# DC-DC_Converter_Module_V1.net
KiCad netlist of a schematic drawn in EAGLE
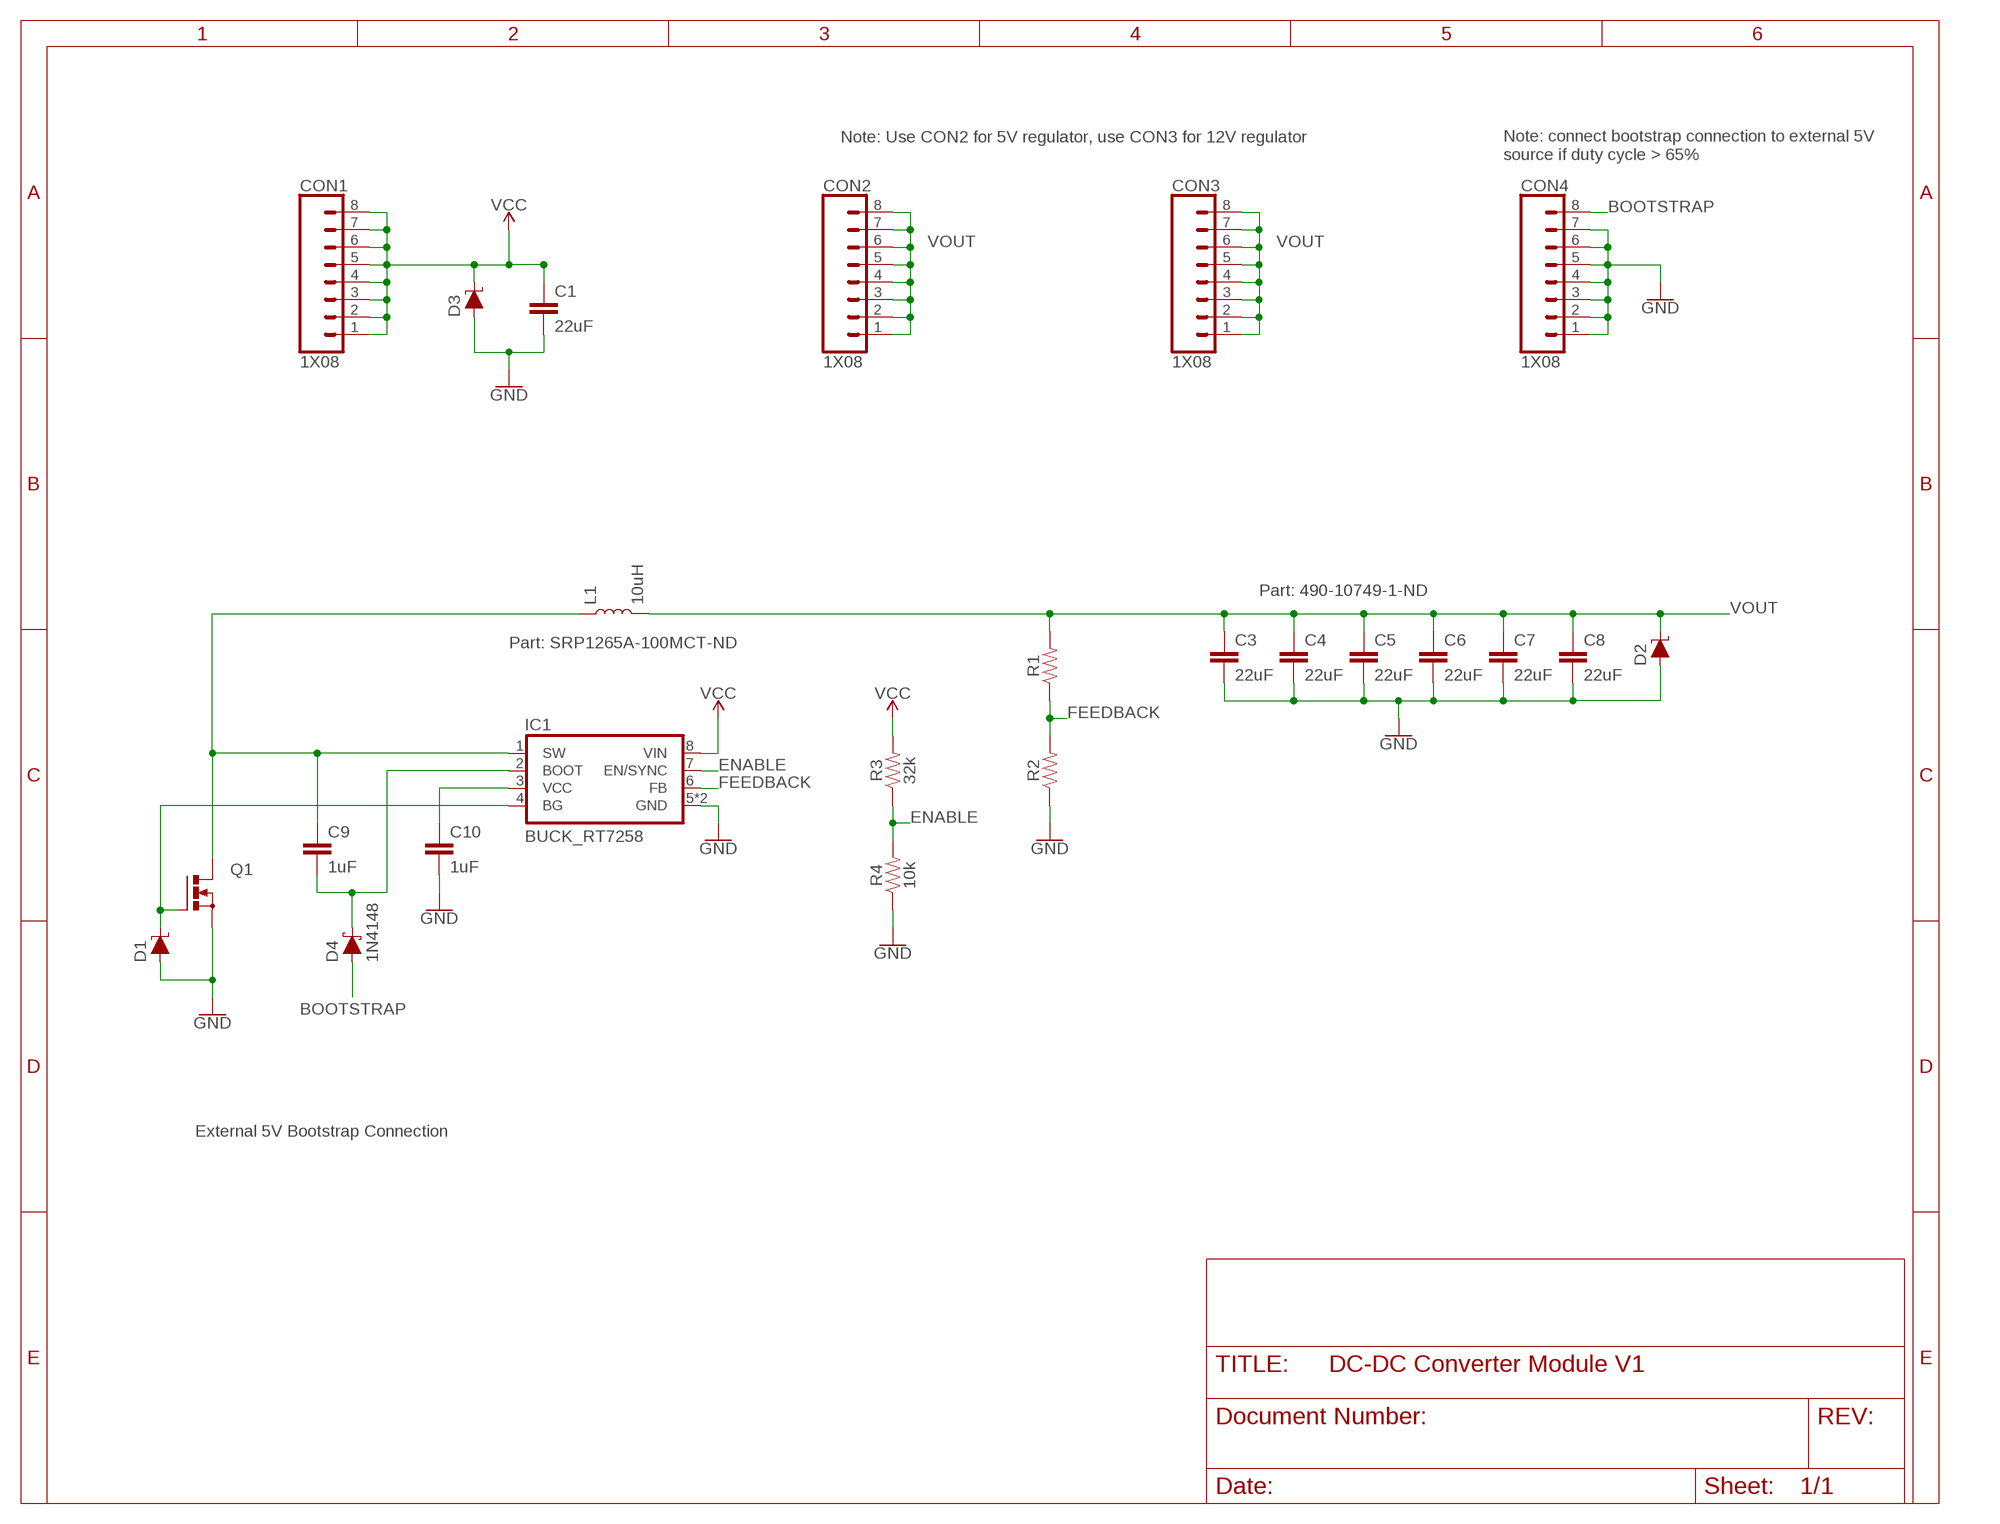
[diagram p0: schematic, sheet 1]

(export (version "E")
  (design (tool "Eeschema 10.0.6"))
  (components
    (comp (ref "C1")
      (value "22uF")
      (footprint "eagle-import:1210")
      (libsource (lib "eagle-import") (part "CAPACITOR_1210"))
    )
    (comp (ref "C3")
      (value "22uF")
      (footprint "eagle-import:0805")
      (libsource (lib "eagle-import") (part "CAPACITOR_0805"))
    )
    (comp (ref "C4")
      (value "22uF")
      (footprint "eagle-import:0805")
      (libsource (lib "eagle-import") (part "CAPACITOR_0805"))
    )
    (comp (ref "C5")
      (value "22uF")
      (footprint "eagle-import:0805")
      (libsource (lib "eagle-import") (part "CAPACITOR_0805"))
    )
    (comp (ref "C6")
      (value "22uF")
      (footprint "eagle-import:0805")
      (libsource (lib "eagle-import") (part "CAPACITOR_0805"))
    )
    (comp (ref "C7")
      (value "22uF")
      (footprint "eagle-import:0805")
      (libsource (lib "eagle-import") (part "CAPACITOR_0805"))
    )
    (comp (ref "C8")
      (value "22uF")
      (footprint "eagle-import:0805")
      (libsource (lib "eagle-import") (part "CAPACITOR_0805"))
    )
    (comp (ref "C9")
      (value "1uF")
      (footprint "eagle-import:0805")
      (libsource (lib "eagle-import") (part "CAPACITOR_0805"))
    )
    (comp (ref "C10")
      (value "1uF")
      (footprint "eagle-import:0805")
      (libsource (lib "eagle-import") (part "CAPACITOR_0805"))
    )
    (comp (ref "CON1")
      (value "1X08")
      (footprint "eagle-import:1X08")
      (libsource (lib "eagle-import") (part "1X08"))
    )
    (comp (ref "CON2")
      (value "1X08")
      (footprint "eagle-import:1X08")
      (libsource (lib "eagle-import") (part "1X08"))
    )
    (comp (ref "CON3")
      (value "1X08")
      (footprint "eagle-import:1X08")
      (libsource (lib "eagle-import") (part "1X08"))
    )
    (comp (ref "CON4")
      (value "1X08")
      (footprint "eagle-import:1X08")
      (libsource (lib "eagle-import") (part "1X08"))
    )
    (comp (ref "D1")
      (value "DIODE_TVS_DO-214AA")
      (footprint "eagle-import:DO214AA")
      (libsource (lib "eagle-import") (part "DIODE_TVS_DO-214AA"))
    )
    (comp (ref "D2")
      (value "DIODE_TVS_DO-214AA")
      (footprint "eagle-import:DO214AA")
      (libsource (lib "eagle-import") (part "DIODE_TVS_DO-214AA"))
    )
    (comp (ref "D3")
      (value "DIODE_TVS_DO-214AA")
      (footprint "eagle-import:DO214AA")
      (libsource (lib "eagle-import") (part "DIODE_TVS_DO-214AA"))
    )
    (comp (ref "D4")
      (value "1N4148")
      (footprint "eagle-import:SOD123FL")
      (libsource (lib "eagle-import") (part "DIODE_SCHOTTKY_SOD123F"))
    )
    (comp (ref "IC1")
      (value "BUCK_RT7258")
      (footprint "eagle-import:SOP-8_HEATSINK")
      (libsource (lib "eagle-import") (part "BUCK_RT7258"))
    )
    (comp (ref "L1")
      (value "10uH")
      (footprint "eagle-import:INDUCTOR_BOURNS_SRP1265A")
      (libsource (lib "eagle-import") (part "INDUCTOR_BOURNS_SRP1265A"))
    )
    (comp (ref "Q1")
      (value "MOSFET_NMOS_TO-263")
      (footprint "eagle-import:TO-263_D2PAK")
      (libsource (lib "eagle-import") (part "MOSFET_NMOS_TO-263"))
    )
    (comp (ref "R1")
      (value "RESISTOR_0805")
      (footprint "eagle-import:0805")
      (libsource (lib "eagle-import") (part "RESISTOR_0805"))
    )
    (comp (ref "R2")
      (value "RESISTOR_0805")
      (footprint "eagle-import:0805")
      (libsource (lib "eagle-import") (part "RESISTOR_0805"))
    )
    (comp (ref "R3")
      (value "32k")
      (footprint "eagle-import:0805")
      (libsource (lib "eagle-import") (part "RESISTOR_0805"))
    )
    (comp (ref "R4")
      (value "10k")
      (footprint "eagle-import:0805")
      (libsource (lib "eagle-import") (part "RESISTOR_0805"))
    )
  )
  (nets
    (net (code "1") (name "/BOOTSTRAP") (class "Default")
      (node (ref "CON4") (pin "8") (pinfunction "8_8") (pintype "passive"))
      (node (ref "D4") (pin "A") (pinfunction "A_A") (pintype "passive"))
    )
    (net (code "2") (name "/ENABLE") (class "Default")
      (node (ref "IC1") (pin "7") (pinfunction "EN/SYNC_7") (pintype "bidirectional"))
      (node (ref "R3") (pin "1") (pinfunction "1_1") (pintype "passive"))
      (node (ref "R4") (pin "2") (pinfunction "2_2") (pintype "passive"))
    )
    (net (code "3") (name "/FEEDBACK") (class "Default")
      (node (ref "IC1") (pin "6") (pinfunction "FB_6") (pintype "bidirectional"))
      (node (ref "R1") (pin "1") (pinfunction "1_1") (pintype "passive"))
      (node (ref "R2") (pin "2") (pinfunction "2_2") (pintype "passive"))
    )
    (net (code "4") (name "/VOUT") (class "Default")
      (node (ref "C3") (pin "1") (pinfunction "1_1") (pintype "passive"))
      (node (ref "C4") (pin "1") (pinfunction "1_1") (pintype "passive"))
      (node (ref "C5") (pin "1") (pinfunction "1_1") (pintype "passive"))
      (node (ref "C6") (pin "1") (pinfunction "1_1") (pintype "passive"))
      (node (ref "C7") (pin "1") (pinfunction "1_1") (pintype "passive"))
      (node (ref "C8") (pin "1") (pinfunction "1_1") (pintype "passive"))
      (node (ref "CON2") (pin "1") (pinfunction "1_1") (pintype "passive"))
      (node (ref "CON2") (pin "2") (pinfunction "2_2") (pintype "passive"))
      (node (ref "CON2") (pin "3") (pinfunction "3_3") (pintype "passive"))
      (node (ref "CON2") (pin "4") (pinfunction "4_4") (pintype "passive"))
      (node (ref "CON2") (pin "5") (pinfunction "5_5") (pintype "passive"))
      (node (ref "CON2") (pin "6") (pinfunction "6_6") (pintype "passive"))
      (node (ref "CON2") (pin "7") (pinfunction "7_7") (pintype "passive"))
      (node (ref "CON2") (pin "8") (pinfunction "8_8") (pintype "passive"))
      (node (ref "CON3") (pin "1") (pinfunction "1_1") (pintype "passive"))
      (node (ref "CON3") (pin "2") (pinfunction "2_2") (pintype "passive"))
      (node (ref "CON3") (pin "3") (pinfunction "3_3") (pintype "passive"))
      (node (ref "CON3") (pin "4") (pinfunction "4_4") (pintype "passive"))
      (node (ref "CON3") (pin "5") (pinfunction "5_5") (pintype "passive"))
      (node (ref "CON3") (pin "6") (pinfunction "6_6") (pintype "passive"))
      (node (ref "CON3") (pin "7") (pinfunction "7_7") (pintype "passive"))
      (node (ref "CON3") (pin "8") (pinfunction "8_8") (pintype "passive"))
      (node (ref "D2") (pin "C") (pinfunction "C_C") (pintype "passive"))
      (node (ref "L1") (pin "2") (pinfunction "2_2") (pintype "passive"))
      (node (ref "R1") (pin "2") (pinfunction "2_2") (pintype "passive"))
    )
    (net (code "5") (name "GND") (class "Default")
      (node (ref "C1") (pin "2") (pinfunction "2_2") (pintype "passive"))
      (node (ref "C10") (pin "2") (pinfunction "2_2") (pintype "passive"))
      (node (ref "C3") (pin "2") (pinfunction "2_2") (pintype "passive"))
      (node (ref "C4") (pin "2") (pinfunction "2_2") (pintype "passive"))
      (node (ref "C5") (pin "2") (pinfunction "2_2") (pintype "passive"))
      (node (ref "C6") (pin "2") (pinfunction "2_2") (pintype "passive"))
      (node (ref "C7") (pin "2") (pinfunction "2_2") (pintype "passive"))
      (node (ref "C8") (pin "2") (pinfunction "2_2") (pintype "passive"))
      (node (ref "CON4") (pin "1") (pinfunction "1_1") (pintype "passive"))
      (node (ref "CON4") (pin "2") (pinfunction "2_2") (pintype "passive"))
      (node (ref "CON4") (pin "3") (pinfunction "3_3") (pintype "passive"))
      (node (ref "CON4") (pin "4") (pinfunction "4_4") (pintype "passive"))
      (node (ref "CON4") (pin "5") (pinfunction "5_5") (pintype "passive"))
      (node (ref "CON4") (pin "6") (pinfunction "6_6") (pintype "passive"))
      (node (ref "CON4") (pin "7") (pinfunction "7_7") (pintype "passive"))
      (node (ref "D1") (pin "A") (pinfunction "A_A") (pintype "passive"))
      (node (ref "D2") (pin "A") (pinfunction "A_A") (pintype "passive"))
      (node (ref "D3") (pin "A") (pinfunction "A_A") (pintype "passive"))
      (node (ref "IC1") (pin "5") (pinfunction "GND_5") (pintype "bidirectional"))
      (node (ref "IC1") (pin "GND") (pinfunction "GND_GND") (pintype "bidirectional"))
      (node (ref "Q1") (pin "3") (pinfunction "S_3") (pintype "passive"))
      (node (ref "R2") (pin "1") (pinfunction "1_1") (pintype "passive"))
      (node (ref "R4") (pin "1") (pinfunction "1_1") (pintype "passive"))
    )
    (net (code "6") (name "Net-(IC1-BG)") (class "Default")
      (node (ref "D1") (pin "C") (pinfunction "C_C") (pintype "passive"))
      (node (ref "IC1") (pin "4") (pinfunction "BG_4") (pintype "bidirectional"))
      (node (ref "Q1") (pin "1") (pinfunction "G_1") (pintype "passive"))
    )
    (net (code "7") (name "Net-(IC1-BOOT)") (class "Default")
      (node (ref "C9") (pin "2") (pinfunction "2_2") (pintype "passive"))
      (node (ref "D4") (pin "C") (pinfunction "C_C") (pintype "passive"))
      (node (ref "IC1") (pin "2") (pinfunction "BOOT_2") (pintype "bidirectional"))
    )
    (net (code "8") (name "Net-(IC1-SW)") (class "Default")
      (node (ref "C9") (pin "1") (pinfunction "1_1") (pintype "passive"))
      (node (ref "IC1") (pin "1") (pinfunction "SW_1") (pintype "bidirectional"))
      (node (ref "L1") (pin "1") (pinfunction "1_1") (pintype "passive"))
      (node (ref "Q1") (pin "2") (pinfunction "D_2") (pintype "passive"))
    )
    (net (code "9") (name "Net-(IC1-VCC)") (class "Default")
      (node (ref "C10") (pin "1") (pinfunction "1_1") (pintype "passive"))
      (node (ref "IC1") (pin "3") (pinfunction "VCC_3") (pintype "bidirectional"))
    )
    (net (code "10") (name "VCC") (class "Default")
      (node (ref "C1") (pin "1") (pinfunction "1_1") (pintype "passive"))
      (node (ref "CON1") (pin "1") (pinfunction "1_1") (pintype "passive"))
      (node (ref "CON1") (pin "2") (pinfunction "2_2") (pintype "passive"))
      (node (ref "CON1") (pin "3") (pinfunction "3_3") (pintype "passive"))
      (node (ref "CON1") (pin "4") (pinfunction "4_4") (pintype "passive"))
      (node (ref "CON1") (pin "5") (pinfunction "5_5") (pintype "passive"))
      (node (ref "CON1") (pin "6") (pinfunction "6_6") (pintype "passive"))
      (node (ref "CON1") (pin "7") (pinfunction "7_7") (pintype "passive"))
      (node (ref "CON1") (pin "8") (pinfunction "8_8") (pintype "passive"))
      (node (ref "D3") (pin "C") (pinfunction "C_C") (pintype "passive"))
      (node (ref "IC1") (pin "8") (pinfunction "VIN_8") (pintype "bidirectional"))
      (node (ref "R3") (pin "2") (pinfunction "2_2") (pintype "passive"))
    )
  )
)
